# Briefkastenmelder.net
KiCad netlist of a schematic drawn in EasyEDA
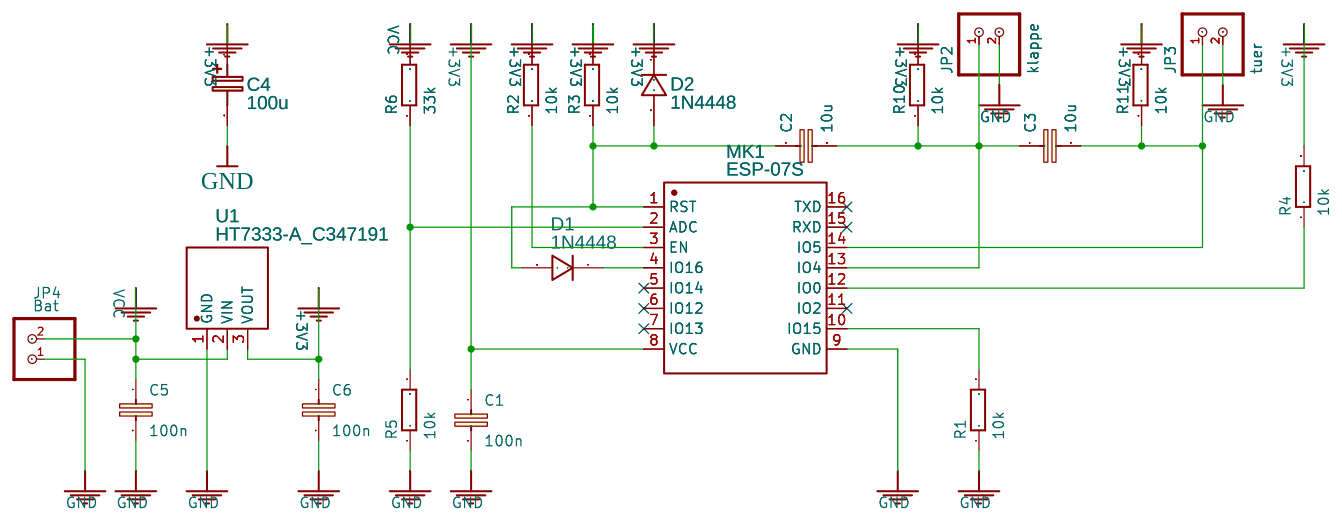
[diagram p0: schematic sheet]

(export (version "E")
  (design (tool "Eeschema 10.0.6"))
  (components
    (comp (ref "C1") (value "100n") (libsource (lib "") (part "Unknown_220_-80")))
    (comp (ref "C2") (value "10u") (libsource (lib "") (part "Unknown_380_-210")))
    (comp (ref "C3") (value "10u") (libsource (lib "") (part "Unknown_500_-210")))
    (comp (ref "C4") (value "100u") (libsource (lib "") (part "Cap_Electrolytic(TH)_D6.3XF2.5_EU")))
    (comp (ref "C5") (value "100n") (libsource (lib "") (part "Unknown_55_-85")))
    (comp (ref "C6") (value "100n") (libsource (lib "") (part "Unknown_145_-85")))
    (comp (ref "D1")
      (value "1N4448")
      (fields (field (name "BOM_Supplier Part") "C54037"))
      (libsource (lib "") (part "Unknown_265_-150"))
    )
    (comp (ref "D2")
      (value "1N4448")
      (fields (field (name "BOM_Supplier Part") "C54037"))
      (libsource (lib "") (part "Unknown_310_-240"))
    )
    (comp (ref "JP2") (value "klappe") (libsource (lib "") (part "Unknown_480_-270")))
    (comp (ref "JP3") (value "tuer") (libsource (lib "") (part "Unknown_590_-270")))
    (comp (ref "JP4") (value "Bat") (libsource (lib "") (part "Unknown_0_-115")))
    (comp (ref "MK1")
      (value "ESP-07S")
      (fields (field (name "BOM_Supplier Part") "C82895"))
      (libsource (lib "") (part "Unknown_355_-145"))
    )
    (comp (ref "R1") (value "10k") (libsource (lib "") (part "Unknown_470_-80")))
    (comp (ref "R2") (value "10k") (libsource (lib "") (part "Unknown_250_-240")))
    (comp (ref "R3") (value "10k") (libsource (lib "") (part "Unknown_280_-240")))
    (comp (ref "R4") (value "10k") (libsource (lib "") (part "Unknown_630_-190")))
    (comp (ref "R5") (value "10k") (libsource (lib "") (part "Unknown_190_-80")))
    (comp (ref "R6") (value "33k") (libsource (lib "") (part "Unknown_190_-240")))
    (comp (ref "R10") (value "10k") (libsource (lib "") (part "Unknown_440_-240")))
    (comp (ref "R11") (value "10k") (libsource (lib "") (part "Unknown_550_-240")))
    (comp (ref "U1")
      (value "HT7333-A_C347191")
      (fields (field (name "BOM_Manufacturer Part") "HT7333-A") (field (name "BOM_Supplier Part") "C347191"))
      (libsource (lib "") (part "HT7333-A_C347191"))
    )
  )
  (nets
    (net (code "1") (name "+3V3") (class "Default")
      (node (ref "C1") (pin "1") (pinfunction "1_1") (pintype "bidirectional"))
      (node (ref "C4") (pin "1") (pinfunction "1_1") (pintype "unspecified"))
      (node (ref "C6") (pin "1") (pinfunction "1_1") (pintype "bidirectional"))
      (node (ref "D2") (pin "1") (pinfunction "K_1") (pintype "unspecified"))
      (node (ref "MK1") (pin "8") (pinfunction "VCC_8") (pintype "unspecified"))
      (node (ref "R10") (pin "2") (pinfunction "2_2") (pintype "bidirectional"))
      (node (ref "R11") (pin "2") (pinfunction "2_2") (pintype "bidirectional"))
      (node (ref "R2") (pin "2") (pinfunction "2_2") (pintype "bidirectional"))
      (node (ref "R3") (pin "2") (pinfunction "2_2") (pintype "bidirectional"))
      (node (ref "R4") (pin "2") (pinfunction "2_2") (pintype "bidirectional"))
      (node (ref "U1") (pin "3") (pinfunction "VOUT_3") (pintype "unspecified"))
    )
    (net (code "2") (name "GND") (class "Default")
      (node (ref "C1") (pin "2") (pinfunction "2_2") (pintype "bidirectional"))
      (node (ref "C4") (pin "2") (pinfunction "2_2") (pintype "unspecified"))
      (node (ref "C5") (pin "2") (pinfunction "2_2") (pintype "bidirectional"))
      (node (ref "C6") (pin "2") (pinfunction "2_2") (pintype "bidirectional"))
      (node (ref "JP2") (pin "2") (pinfunction "2_2") (pintype "bidirectional"))
      (node (ref "JP3") (pin "2") (pinfunction "2_2") (pintype "bidirectional"))
      (node (ref "JP4") (pin "1") (pinfunction "1_1") (pintype "bidirectional"))
      (node (ref "MK1") (pin "9") (pinfunction "GND_9") (pintype "unspecified"))
      (node (ref "R1") (pin "1") (pinfunction "1_1") (pintype "bidirectional"))
      (node (ref "R5") (pin "1") (pinfunction "1_1") (pintype "bidirectional"))
      (node (ref "U1") (pin "1") (pinfunction "GND_1") (pintype "unspecified"))
    )
    (net (code "3") (name "Net-(D1-A)") (class "Default")
      (node (ref "C2") (pin "1") (pinfunction "1_1") (pintype "bidirectional"))
      (node (ref "D1") (pin "2") (pinfunction "A_2") (pintype "unspecified"))
      (node (ref "D2") (pin "2") (pinfunction "A_2") (pintype "unspecified"))
      (node (ref "MK1") (pin "1") (pinfunction "RST_1") (pintype "unspecified"))
      (node (ref "R3") (pin "1") (pinfunction "1_1") (pintype "bidirectional"))
    )
    (net (code "4") (name "Net-(D1-K)") (class "Default")
      (node (ref "D1") (pin "1") (pinfunction "K_1") (pintype "unspecified"))
      (node (ref "MK1") (pin "4") (pinfunction "IO16_4") (pintype "unspecified"))
    )
    (net (code "5") (name "Net-(MK1-ADC)") (class "Default")
      (node (ref "MK1") (pin "2") (pinfunction "ADC_2") (pintype "unspecified"))
      (node (ref "R5") (pin "2") (pinfunction "2_2") (pintype "bidirectional"))
      (node (ref "R6") (pin "1") (pinfunction "1_1") (pintype "bidirectional"))
    )
    (net (code "6") (name "Net-(MK1-EN)") (class "Default")
      (node (ref "MK1") (pin "3") (pinfunction "EN_3") (pintype "unspecified"))
      (node (ref "R2") (pin "1") (pinfunction "1_1") (pintype "bidirectional"))
    )
    (net (code "7") (name "Net-(MK1-IO0)") (class "Default")
      (node (ref "MK1") (pin "12") (pinfunction "IO0_12") (pintype "unspecified"))
      (node (ref "R4") (pin "1") (pinfunction "1_1") (pintype "bidirectional"))
    )
    (net (code "8") (name "Net-(MK1-IO4)") (class "Default")
      (node (ref "C2") (pin "2") (pinfunction "2_2") (pintype "bidirectional"))
      (node (ref "C3") (pin "1") (pinfunction "1_1") (pintype "bidirectional"))
      (node (ref "JP2") (pin "1") (pinfunction "1_1") (pintype "bidirectional"))
      (node (ref "MK1") (pin "13") (pinfunction "IO4_13") (pintype "unspecified"))
      (node (ref "R10") (pin "1") (pinfunction "1_1") (pintype "bidirectional"))
    )
    (net (code "9") (name "Net-(MK1-IO5)") (class "Default")
      (node (ref "C3") (pin "2") (pinfunction "2_2") (pintype "bidirectional"))
      (node (ref "JP3") (pin "1") (pinfunction "1_1") (pintype "bidirectional"))
      (node (ref "MK1") (pin "14") (pinfunction "IO5_14") (pintype "unspecified"))
      (node (ref "R11") (pin "1") (pinfunction "1_1") (pintype "bidirectional"))
    )
    (net (code "10") (name "Net-(MK1-IO15)") (class "Default")
      (node (ref "MK1") (pin "10") (pinfunction "IO15_10") (pintype "unspecified"))
      (node (ref "R1") (pin "2") (pinfunction "2_2") (pintype "bidirectional"))
    )
    (net (code "11") (name "VCC") (class "Default")
      (node (ref "C5") (pin "1") (pinfunction "1_1") (pintype "bidirectional"))
      (node (ref "JP4") (pin "2") (pinfunction "2_2") (pintype "bidirectional"))
      (node (ref "R6") (pin "2") (pinfunction "2_2") (pintype "bidirectional"))
      (node (ref "U1") (pin "2") (pinfunction "VIN_2") (pintype "unspecified"))
    )
    (net (code "12") (name "unconnected-(MK1-IO2-Pad11)") (class "Default")
      (node (ref "MK1") (pin "11") (pinfunction "IO2_11") (pintype "unspecified+no_connect"))
    )
    (net (code "13") (name "unconnected-(MK1-IO12-Pad6)") (class "Default")
      (node (ref "MK1") (pin "6") (pinfunction "IO12_6") (pintype "unspecified+no_connect"))
    )
    (net (code "14") (name "unconnected-(MK1-IO13-Pad7)") (class "Default")
      (node (ref "MK1") (pin "7") (pinfunction "IO13_7") (pintype "unspecified+no_connect"))
    )
    (net (code "15") (name "unconnected-(MK1-IO14-Pad5)") (class "Default")
      (node (ref "MK1") (pin "5") (pinfunction "IO14_5") (pintype "unspecified+no_connect"))
    )
    (net (code "16") (name "unconnected-(MK1-RXD-Pad15)") (class "Default")
      (node (ref "MK1") (pin "15") (pinfunction "RXD_15") (pintype "unspecified+no_connect"))
    )
    (net (code "17") (name "unconnected-(MK1-TXD-Pad16)") (class "Default")
      (node (ref "MK1") (pin "16") (pinfunction "TXD_16") (pintype "unspecified+no_connect"))
    )
  )
)
